# IR_analog.net
KiCad netlist of a schematic drawn in EAGLE
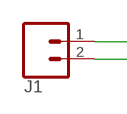
[diagram p0: schematic, sheet 1, part 1 of 2]
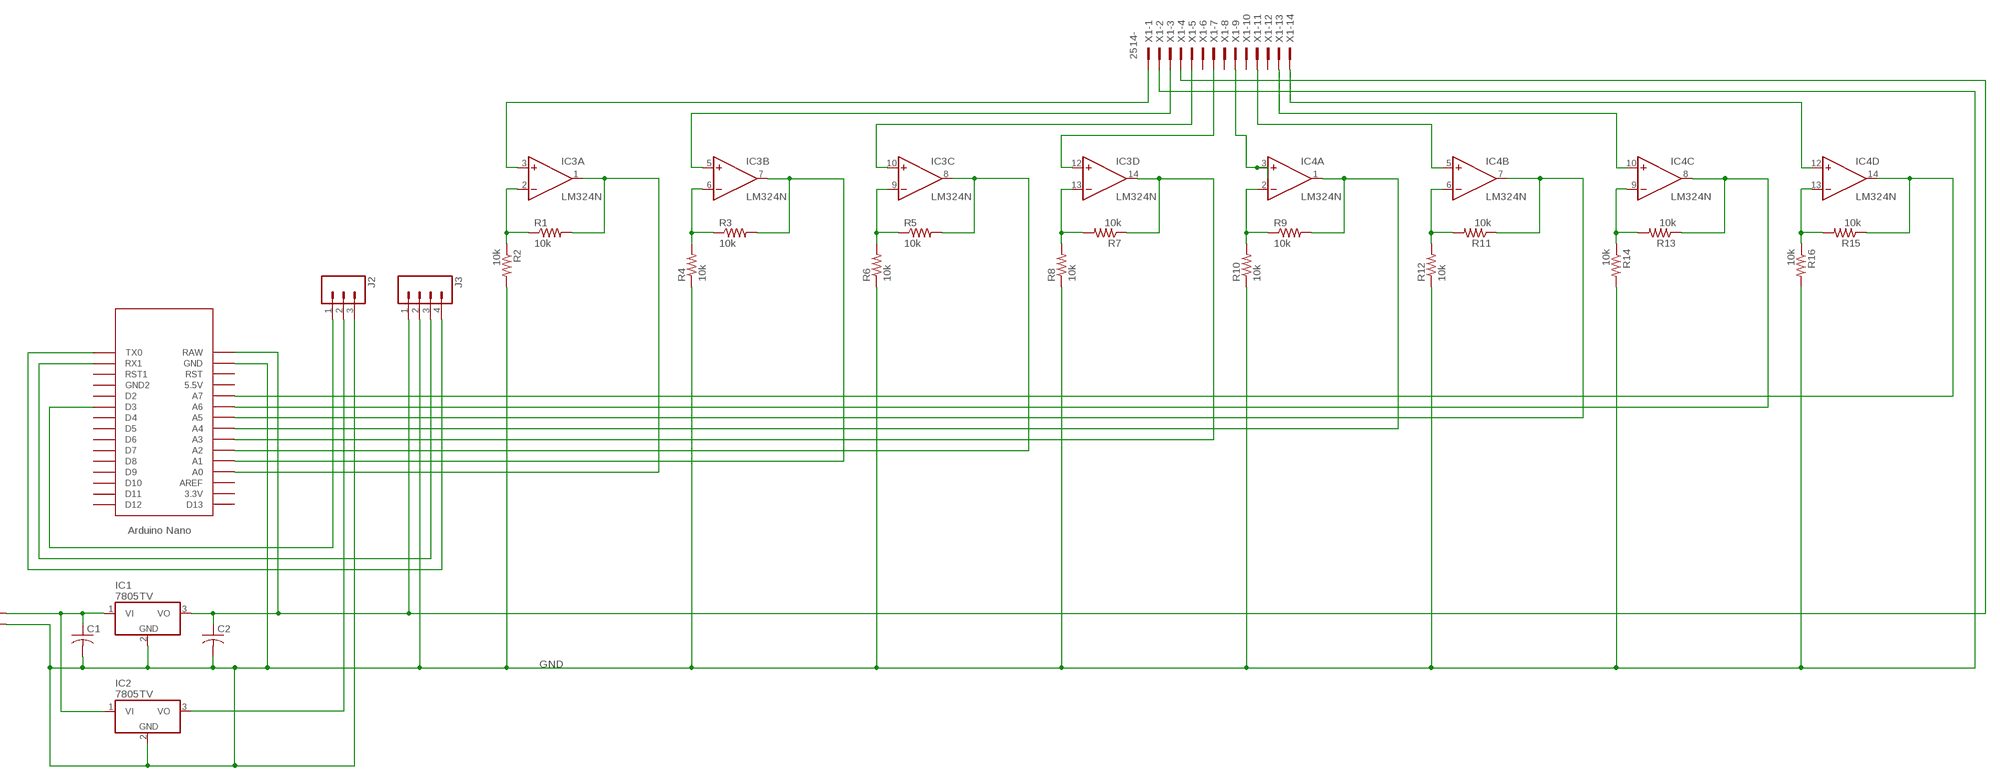
[diagram p1: schematic, sheet 1, part 2 of 2]

(export (version "E")
  (design (tool "Eeschema 10.0.6"))
  (components
    (comp (ref "C1")
      (value "C-US025-060X050")
      (footprint "eagle-import:C025-060X050")
      (libsource (lib "eagle-import") (part "C-US025-060X050"))
    )
    (comp (ref "C2")
      (value "C-US025-060X050")
      (footprint "eagle-import:C025-060X050")
      (libsource (lib "eagle-import") (part "C-US025-060X050"))
    )
    (comp (ref "IC1")
      (value "7805TV")
      (footprint "eagle-import:TO220V")
      (libsource (lib "eagle-import") (part "78TV05"))
    )
    (comp (ref "IC2")
      (value "7805TV")
      (footprint "eagle-import:TO220V")
      (libsource (lib "eagle-import") (part "78TV05"))
    )
    (comp (ref "IC3")
      (value "LM324N")
      (footprint "eagle-import:DIL14")
      (libsource (lib "eagle-import") (part "LM324N"))
    )
    (comp (ref "IC4")
      (value "LM324N")
      (footprint "eagle-import:DIL14")
      (libsource (lib "eagle-import") (part "LM324N"))
    )
    (comp (ref "J1")
      (value "CONN_023.5MM_LOCK")
      (footprint "eagle-import:SCREWTERMINAL-3.5MM-2_LOCK")
      (libsource (lib "eagle-import") (part "CONN_023.5MM_LOCK"))
    )
    (comp (ref "J2")
      (value "CONN_03LONGPADS")
      (footprint "eagle-import:1X03_LONGPADS")
      (libsource (lib "eagle-import") (part "CONN_03LONGPADS"))
    )
    (comp (ref "J3")
      (value "CONN_04LONGPADS")
      (footprint "eagle-import:1X04_LONGPADS")
      (libsource (lib "eagle-import") (part "CONN_04LONGPADS"))
    )
    (comp (ref "R1")
      (value "10k")
      (footprint "eagle-import:0204_5")
      (libsource (lib "eagle-import") (part "R-US_0204/5"))
    )
    (comp (ref "R2")
      (value "10k")
      (footprint "eagle-import:0204_5")
      (libsource (lib "eagle-import") (part "R-US_0204/5"))
    )
    (comp (ref "R3")
      (value "10k")
      (footprint "eagle-import:0204_5")
      (libsource (lib "eagle-import") (part "R-US_0204/5"))
    )
    (comp (ref "R4")
      (value "10k")
      (footprint "eagle-import:0204_5")
      (libsource (lib "eagle-import") (part "R-US_0204/5"))
    )
    (comp (ref "R5")
      (value "10k")
      (footprint "eagle-import:0204_5")
      (libsource (lib "eagle-import") (part "R-US_0204/5"))
    )
    (comp (ref "R6")
      (value "10k")
      (footprint "eagle-import:0204_5")
      (libsource (lib "eagle-import") (part "R-US_0204/5"))
    )
    (comp (ref "R7")
      (value "10k")
      (footprint "eagle-import:0204_5")
      (libsource (lib "eagle-import") (part "R-US_0204/5"))
    )
    (comp (ref "R8")
      (value "10k")
      (footprint "eagle-import:0204_5")
      (libsource (lib "eagle-import") (part "R-US_0204/5"))
    )
    (comp (ref "R9")
      (value "10k")
      (footprint "eagle-import:0204_5")
      (libsource (lib "eagle-import") (part "R-US_0204/5"))
    )
    (comp (ref "R10")
      (value "10k")
      (footprint "eagle-import:0204_5")
      (libsource (lib "eagle-import") (part "R-US_0204/5"))
    )
    (comp (ref "R11")
      (value "10k")
      (footprint "eagle-import:0204_5")
      (libsource (lib "eagle-import") (part "R-US_0204/5"))
    )
    (comp (ref "R12")
      (value "10k")
      (footprint "eagle-import:0204_5")
      (libsource (lib "eagle-import") (part "R-US_0204/5"))
    )
    (comp (ref "R13")
      (value "10k")
      (footprint "eagle-import:0204_5")
      (libsource (lib "eagle-import") (part "R-US_0204/5"))
    )
    (comp (ref "R14")
      (value "10k")
      (footprint "eagle-import:0204_5")
      (libsource (lib "eagle-import") (part "R-US_0204/5"))
    )
    (comp (ref "R15")
      (value "10k")
      (footprint "eagle-import:0204_5")
      (libsource (lib "eagle-import") (part "R-US_0204/5"))
    )
    (comp (ref "R16")
      (value "10k")
      (footprint "eagle-import:0204_5")
      (libsource (lib "eagle-import") (part "R-US_0204/5"))
    )
    (comp (ref "U$1")
      (value "NANO")
      (footprint "eagle-import:NANO")
      (libsource (lib "eagle-import") (part "NANO"))
    )
    (comp (ref "X1")
      (value "2514-")
      (footprint "eagle-import:PAK100_2500-14")
      (libsource (lib "eagle-import") (part "2514-"))
    )
  )
  (nets
    (net (code "1") (name "/GND") (class "Default")
      (node (ref "C1") (pin "2") (pinfunction "2_2") (pintype "passive"))
      (node (ref "C2") (pin "2") (pinfunction "2_2") (pintype "passive"))
      (node (ref "IC1") (pin "2") (pinfunction "GND_2") (pintype "passive"))
      (node (ref "IC2") (pin "2") (pinfunction "GND_2") (pintype "passive"))
      (node (ref "J1") (pin "2") (pinfunction "2_2") (pintype "passive"))
      (node (ref "J2") (pin "3") (pinfunction "3_3") (pintype "passive"))
      (node (ref "J3") (pin "2") (pinfunction "2_2") (pintype "passive"))
      (node (ref "R10") (pin "1") (pinfunction "1_1") (pintype "passive"))
      (node (ref "R12") (pin "1") (pinfunction "1_1") (pintype "passive"))
      (node (ref "R14") (pin "2") (pinfunction "2_2") (pintype "passive"))
      (node (ref "R16") (pin "2") (pinfunction "2_2") (pintype "passive"))
      (node (ref "R2") (pin "2") (pinfunction "2_2") (pintype "passive"))
      (node (ref "R4") (pin "1") (pinfunction "1_1") (pintype "passive"))
      (node (ref "R6") (pin "1") (pinfunction "1_1") (pintype "passive"))
      (node (ref "R8") (pin "1") (pinfunction "1_1") (pintype "passive"))
      (node (ref "U$1") (pin "GND") (pinfunction "GND_GND") (pintype "bidirectional"))
      (node (ref "X1") (pin "2") (pinfunction "KL_2") (pintype "passive"))
    )
    (net (code "2") (name "Net-(IC1-VI)") (class "Default")
      (node (ref "C1") (pin "1") (pinfunction "1_1") (pintype "passive"))
      (node (ref "IC1") (pin "1") (pinfunction "VI_1") (pintype "input"))
      (node (ref "IC2") (pin "1") (pinfunction "VI_1") (pintype "input"))
      (node (ref "J1") (pin "1") (pinfunction "1_1") (pintype "passive"))
    )
    (net (code "3") (name "Net-(IC1-VO)") (class "Default")
      (node (ref "C2") (pin "1") (pinfunction "1_1") (pintype "passive"))
      (node (ref "IC1") (pin "3") (pinfunction "VO_3") (pintype "passive"))
      (node (ref "J3") (pin "1") (pinfunction "1_1") (pintype "passive"))
      (node (ref "U$1") (pin "RAW") (pinfunction "RAW_RAW") (pintype "bidirectional"))
      (node (ref "X1") (pin "4") (pinfunction "KL_4") (pintype "passive"))
    )
    (net (code "4") (name "Net-(IC2-VO)") (class "Default")
      (node (ref "IC2") (pin "3") (pinfunction "VO_3") (pintype "passive"))
      (node (ref "J2") (pin "2") (pinfunction "2_2") (pintype "passive"))
    )
    (net (code "5") (name "Net-(IC3A-+IN)") (class "Default")
      (node (ref "IC3") (pin "3") (pinfunction "+IN_3") (pintype "input"))
      (node (ref "X1") (pin "1") (pinfunction "KL_1") (pintype "passive"))
    )
    (net (code "6") (name "Net-(IC3A--IN)") (class "Default")
      (node (ref "IC3") (pin "2") (pinfunction "-IN_2") (pintype "input"))
      (node (ref "R1") (pin "1") (pinfunction "1_1") (pintype "passive"))
      (node (ref "R2") (pin "1") (pinfunction "1_1") (pintype "passive"))
    )
    (net (code "7") (name "Net-(IC3A-OUT)") (class "Default")
      (node (ref "IC3") (pin "1") (pinfunction "OUT_1") (pintype "output"))
      (node (ref "R1") (pin "2") (pinfunction "2_2") (pintype "passive"))
      (node (ref "U$1") (pin "A0") (pinfunction "A0_A0") (pintype "bidirectional"))
    )
    (net (code "8") (name "Net-(IC3B-+IN)") (class "Default")
      (node (ref "IC3") (pin "5") (pinfunction "+IN_5") (pintype "input"))
      (node (ref "X1") (pin "3") (pinfunction "KL_3") (pintype "passive"))
    )
    (net (code "9") (name "Net-(IC3B--IN)") (class "Default")
      (node (ref "IC3") (pin "6") (pinfunction "-IN_6") (pintype "input"))
      (node (ref "R3") (pin "1") (pinfunction "1_1") (pintype "passive"))
      (node (ref "R4") (pin "2") (pinfunction "2_2") (pintype "passive"))
    )
    (net (code "10") (name "Net-(IC3B-OUT)") (class "Default")
      (node (ref "IC3") (pin "7") (pinfunction "OUT_7") (pintype "output"))
      (node (ref "R3") (pin "2") (pinfunction "2_2") (pintype "passive"))
      (node (ref "U$1") (pin "A1") (pinfunction "A1_A1") (pintype "bidirectional"))
    )
    (net (code "11") (name "Net-(IC3C-+IN)") (class "Default")
      (node (ref "IC3") (pin "10") (pinfunction "+IN_10") (pintype "input"))
      (node (ref "X1") (pin "5") (pinfunction "KL_5") (pintype "passive"))
    )
    (net (code "12") (name "Net-(IC3C--IN)") (class "Default")
      (node (ref "IC3") (pin "9") (pinfunction "-IN_9") (pintype "input"))
      (node (ref "R5") (pin "1") (pinfunction "1_1") (pintype "passive"))
      (node (ref "R6") (pin "2") (pinfunction "2_2") (pintype "passive"))
    )
    (net (code "13") (name "Net-(IC3C-OUT)") (class "Default")
      (node (ref "IC3") (pin "8") (pinfunction "OUT_8") (pintype "output"))
      (node (ref "R5") (pin "2") (pinfunction "2_2") (pintype "passive"))
      (node (ref "U$1") (pin "A2") (pinfunction "A2_A2") (pintype "bidirectional"))
    )
    (net (code "14") (name "Net-(IC3D-+IN)") (class "Default")
      (node (ref "IC3") (pin "12") (pinfunction "+IN_12") (pintype "input"))
      (node (ref "X1") (pin "7") (pinfunction "KL_7") (pintype "passive"))
    )
    (net (code "15") (name "Net-(IC3D--IN)") (class "Default")
      (node (ref "IC3") (pin "13") (pinfunction "-IN_13") (pintype "input"))
      (node (ref "R7") (pin "2") (pinfunction "2_2") (pintype "passive"))
      (node (ref "R8") (pin "2") (pinfunction "2_2") (pintype "passive"))
    )
    (net (code "16") (name "Net-(IC3D-OUT)") (class "Default")
      (node (ref "IC3") (pin "14") (pinfunction "OUT_14") (pintype "output"))
      (node (ref "R7") (pin "1") (pinfunction "1_1") (pintype "passive"))
      (node (ref "U$1") (pin "A3") (pinfunction "A3_A3") (pintype "bidirectional"))
    )
    (net (code "17") (name "Net-(IC4A-+IN)") (class "Default")
      (node (ref "IC4") (pin "3") (pinfunction "+IN_3") (pintype "input"))
      (node (ref "X1") (pin "9") (pinfunction "KL_9") (pintype "passive"))
    )
    (net (code "18") (name "Net-(IC4A--IN)") (class "Default")
      (node (ref "IC4") (pin "2") (pinfunction "-IN_2") (pintype "input"))
      (node (ref "R10") (pin "2") (pinfunction "2_2") (pintype "passive"))
      (node (ref "R9") (pin "1") (pinfunction "1_1") (pintype "passive"))
    )
    (net (code "19") (name "Net-(IC4A-OUT)") (class "Default")
      (node (ref "IC4") (pin "1") (pinfunction "OUT_1") (pintype "output"))
      (node (ref "R9") (pin "2") (pinfunction "2_2") (pintype "passive"))
      (node (ref "U$1") (pin "A4") (pinfunction "A4_A4") (pintype "bidirectional"))
    )
    (net (code "20") (name "Net-(IC4B-+IN)") (class "Default")
      (node (ref "IC4") (pin "5") (pinfunction "+IN_5") (pintype "input"))
      (node (ref "X1") (pin "11") (pinfunction "KL_11") (pintype "passive"))
    )
    (net (code "21") (name "Net-(IC4B--IN)") (class "Default")
      (node (ref "IC4") (pin "6") (pinfunction "-IN_6") (pintype "input"))
      (node (ref "R11") (pin "2") (pinfunction "2_2") (pintype "passive"))
      (node (ref "R12") (pin "2") (pinfunction "2_2") (pintype "passive"))
    )
    (net (code "22") (name "Net-(IC4B-OUT)") (class "Default")
      (node (ref "IC4") (pin "7") (pinfunction "OUT_7") (pintype "output"))
      (node (ref "R11") (pin "1") (pinfunction "1_1") (pintype "passive"))
      (node (ref "U$1") (pin "A5") (pinfunction "A5_A5") (pintype "bidirectional"))
    )
    (net (code "23") (name "Net-(IC4C-+IN)") (class "Default")
      (node (ref "IC4") (pin "10") (pinfunction "+IN_10") (pintype "input"))
      (node (ref "X1") (pin "13") (pinfunction "KL_13") (pintype "passive"))
    )
    (net (code "24") (name "Net-(IC4C--IN)") (class "Default")
      (node (ref "IC4") (pin "9") (pinfunction "-IN_9") (pintype "input"))
      (node (ref "R13") (pin "2") (pinfunction "2_2") (pintype "passive"))
      (node (ref "R14") (pin "1") (pinfunction "1_1") (pintype "passive"))
    )
    (net (code "25") (name "Net-(IC4C-OUT)") (class "Default")
      (node (ref "IC4") (pin "8") (pinfunction "OUT_8") (pintype "output"))
      (node (ref "R13") (pin "1") (pinfunction "1_1") (pintype "passive"))
      (node (ref "U$1") (pin "A6") (pinfunction "A6_A6") (pintype "bidirectional"))
    )
    (net (code "26") (name "Net-(IC4D-+IN)") (class "Default")
      (node (ref "IC4") (pin "12") (pinfunction "+IN_12") (pintype "input"))
      (node (ref "X1") (pin "14") (pinfunction "KL_14") (pintype "passive"))
    )
    (net (code "27") (name "Net-(IC4D--IN)") (class "Default")
      (node (ref "IC4") (pin "13") (pinfunction "-IN_13") (pintype "input"))
      (node (ref "R15") (pin "2") (pinfunction "2_2") (pintype "passive"))
      (node (ref "R16") (pin "1") (pinfunction "1_1") (pintype "passive"))
    )
    (net (code "28") (name "Net-(IC4D-OUT)") (class "Default")
      (node (ref "IC4") (pin "14") (pinfunction "OUT_14") (pintype "output"))
      (node (ref "R15") (pin "1") (pinfunction "1_1") (pintype "passive"))
      (node (ref "U$1") (pin "A7") (pinfunction "A7_A7") (pintype "bidirectional"))
    )
    (net (code "29") (name "Net-(J2-Pad1)") (class "Default")
      (node (ref "J2") (pin "1") (pinfunction "1_1") (pintype "passive"))
      (node (ref "U$1") (pin "D3") (pinfunction "D3_D3") (pintype "bidirectional"))
    )
    (net (code "30") (name "Net-(J3-Pad3)") (class "Default")
      (node (ref "J3") (pin "3") (pinfunction "3_3") (pintype "passive"))
      (node (ref "U$1") (pin "RX1") (pinfunction "RX1_RX1") (pintype "bidirectional"))
    )
    (net (code "31") (name "Net-(J3-Pad4)") (class "Default")
      (node (ref "J3") (pin "4") (pinfunction "4_4") (pintype "passive"))
      (node (ref "U$1") (pin "TX0") (pinfunction "TX0_TX0") (pintype "bidirectional"))
    )
    (net (code "32") (name "unconnected-(U$1-5.5V-Pad5V)") (class "Default")
      (node (ref "U$1") (pin "5V") (pinfunction "5.5V_5V") (pintype "bidirectional"))
    )
    (net (code "33") (name "unconnected-(U$1-GND2-PadGND1)") (class "Default")
      (node (ref "U$1") (pin "GND1") (pinfunction "GND2_GND1") (pintype "bidirectional"))
    )
    (net (code "34") (name "unconnected-(U$1-Pad3.3V)") (class "Default")
      (node (ref "U$1") (pin "3.3V") (pinfunction "3.3V_3.3V") (pintype "bidirectional"))
    )
    (net (code "35") (name "unconnected-(U$1-PadAREF)") (class "Default")
      (node (ref "U$1") (pin "AREF") (pinfunction "AREF_AREF") (pintype "bidirectional"))
    )
    (net (code "36") (name "unconnected-(U$1-PadD2)") (class "Default")
      (node (ref "U$1") (pin "D2") (pinfunction "D2_D2") (pintype "bidirectional"))
    )
    (net (code "37") (name "unconnected-(U$1-PadD4)") (class "Default")
      (node (ref "U$1") (pin "D4") (pinfunction "D4_D4") (pintype "bidirectional"))
    )
    (net (code "38") (name "unconnected-(U$1-PadD5)") (class "Default")
      (node (ref "U$1") (pin "D5") (pinfunction "D5_D5") (pintype "bidirectional"))
    )
    (net (code "39") (name "unconnected-(U$1-PadD6)") (class "Default")
      (node (ref "U$1") (pin "D6") (pinfunction "D6_D6") (pintype "bidirectional"))
    )
    (net (code "40") (name "unconnected-(U$1-PadD7)") (class "Default")
      (node (ref "U$1") (pin "D7") (pinfunction "D7_D7") (pintype "bidirectional"))
    )
    (net (code "41") (name "unconnected-(U$1-PadD8)") (class "Default")
      (node (ref "U$1") (pin "D8") (pinfunction "D8_D8") (pintype "bidirectional"))
    )
    (net (code "42") (name "unconnected-(U$1-PadD9)") (class "Default")
      (node (ref "U$1") (pin "D9") (pinfunction "D9_D9") (pintype "bidirectional"))
    )
    (net (code "43") (name "unconnected-(U$1-PadD10)") (class "Default")
      (node (ref "U$1") (pin "D10") (pinfunction "D10_D10") (pintype "bidirectional"))
    )
    (net (code "44") (name "unconnected-(U$1-PadD11)") (class "Default")
      (node (ref "U$1") (pin "D11") (pinfunction "D11_D11") (pintype "bidirectional"))
    )
    (net (code "45") (name "unconnected-(U$1-PadD12)") (class "Default")
      (node (ref "U$1") (pin "D12") (pinfunction "D12_D12") (pintype "bidirectional"))
    )
    (net (code "46") (name "unconnected-(U$1-PadD13)") (class "Default")
      (node (ref "U$1") (pin "D13") (pinfunction "D13_D13") (pintype "bidirectional"))
    )
    (net (code "47") (name "unconnected-(U$1-PadICSP1)") (class "Default")
      (node (ref "U$1") (pin "ICSP1") (pinfunction "ICSP1_ICSP1") (pintype "bidirectional"))
    )
    (net (code "48") (name "unconnected-(U$1-PadICSP2)") (class "Default")
      (node (ref "U$1") (pin "ICSP2") (pinfunction "ICSP2_ICSP2") (pintype "bidirectional"))
    )
    (net (code "49") (name "unconnected-(U$1-PadICSP3)") (class "Default")
      (node (ref "U$1") (pin "ICSP3") (pinfunction "ICSP3_ICSP3") (pintype "bidirectional"))
    )
    (net (code "50") (name "unconnected-(U$1-PadICSP4)") (class "Default")
      (node (ref "U$1") (pin "ICSP4") (pinfunction "ICSP4_ICSP4") (pintype "bidirectional"))
    )
    (net (code "51") (name "unconnected-(U$1-PadICSP5)") (class "Default")
      (node (ref "U$1") (pin "ICSP5") (pinfunction "ICSP5_ICSP5") (pintype "bidirectional"))
    )
    (net (code "52") (name "unconnected-(U$1-PadICSP6)") (class "Default")
      (node (ref "U$1") (pin "ICSP6") (pinfunction "ICSP6_ICSP6") (pintype "bidirectional"))
    )
    (net (code "53") (name "unconnected-(U$1-PadRST)") (class "Default")
      (node (ref "U$1") (pin "RST") (pinfunction "RST_RST") (pintype "bidirectional"))
    )
    (net (code "54") (name "unconnected-(U$1-PadRST1)") (class "Default")
      (node (ref "U$1") (pin "RST1") (pinfunction "RST1_RST1") (pintype "bidirectional"))
    )
    (net (code "55") (name "unconnected-(X1B-KL-Pad10)") (class "Default")
      (node (ref "X1") (pin "10") (pinfunction "KL_10") (pintype "passive"))
    )
    (net (code "56") (name "unconnected-(X1D-KL-Pad12)") (class "Default")
      (node (ref "X1") (pin "12") (pinfunction "KL_12") (pintype "passive"))
    )
    (net (code "57") (name "unconnected-(X1K-KL-Pad6)") (class "Default")
      (node (ref "X1") (pin "6") (pinfunction "KL_6") (pintype "passive"))
    )
    (net (code "58") (name "unconnected-(X1M-KL-Pad8)") (class "Default")
      (node (ref "X1") (pin "8") (pinfunction "KL_8") (pintype "passive"))
    )
  )
)
